# STM32F4_CPU.net
KiCad netlist of a schematic drawn in Altium Designer
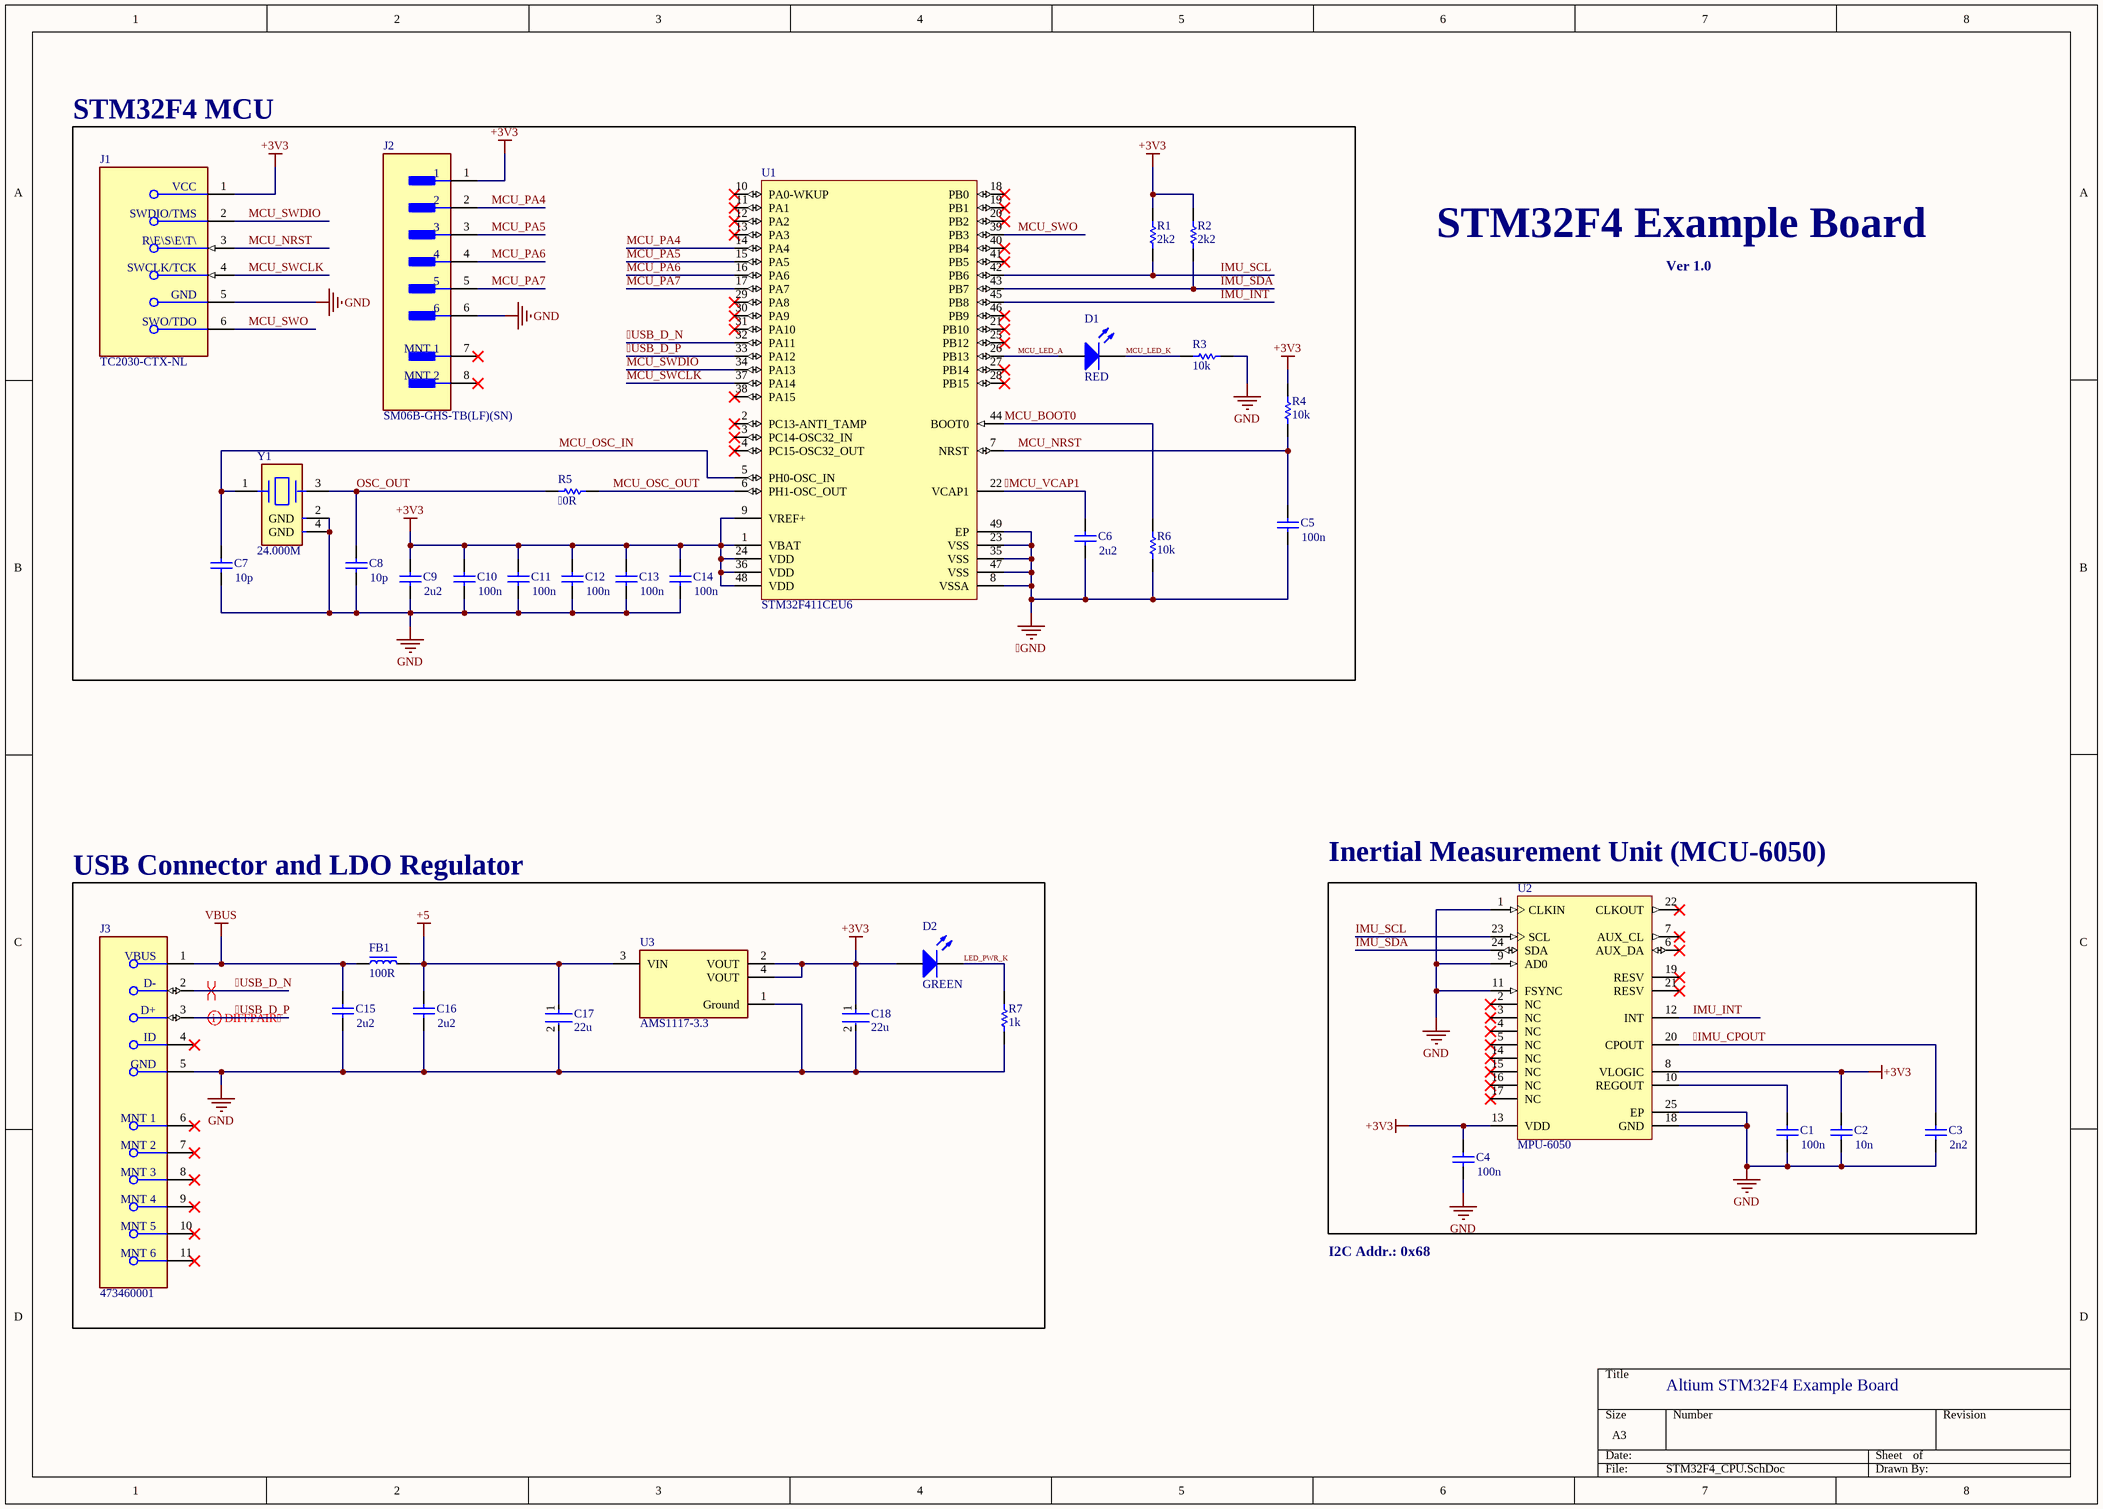
[diagram p0: STM32F4_CPU.SchDoc]

(export (version "E")
  (design (tool "Eeschema 10.0.6"))
  (components
    (comp (ref "C1")
      (value "100n")
      (footprint "0402")
      (description "Capacitor (Semiconductor SIM Model)")
      (fields (field (name "Comment") "Cap Semi") (field (name "PUBLISHER") "Altium Limited"))
      (libsource (lib "Miscellaneous Devices") (part "Cap Semi"))
    )
    (comp (ref "C2")
      (value "10n")
      (footprint "0402")
      (description "Capacitor (Semiconductor SIM Model)")
      (fields (field (name "Comment") "Cap Semi") (field (name "PUBLISHER") "Altium Limited"))
      (libsource (lib "Miscellaneous Devices") (part "Cap Semi"))
    )
    (comp (ref "C3")
      (value "2n2")
      (footprint "0402")
      (description "Capacitor (Semiconductor SIM Model)")
      (fields (field (name "Comment") "Cap Semi") (field (name "PUBLISHER") "Altium Limited"))
      (libsource (lib "Miscellaneous Devices") (part "Cap Semi"))
    )
    (comp (ref "C4")
      (value "100n")
      (footprint "0402")
      (description "Capacitor (Semiconductor SIM Model)")
      (fields (field (name "Comment") "Cap Semi") (field (name "PUBLISHER") "Altium Limited"))
      (libsource (lib "Miscellaneous Devices") (part "Cap Semi"))
    )
    (comp (ref "C5")
      (value "100n")
      (footprint "0402")
      (description "Capacitor (Semiconductor SIM Model)")
      (fields (field (name "Comment") "Cap Semi") (field (name "PUBLISHER") "Altium Limited"))
      (libsource (lib "Miscellaneous Devices") (part "Cap Semi"))
    )
    (comp (ref "C6")
      (value "2u2")
      (footprint "1608[0603]")
      (description "Capacitor (Semiconductor SIM Model)")
      (fields (field (name "Comment") "Cap Semi") (field (name "PUBLISHER") "Altium Limited"))
      (libsource (lib "Miscellaneous Devices") (part "Cap Semi"))
    )
    (comp (ref "C7")
      (value "10p")
      (footprint "0402")
      (description "Capacitor (Semiconductor SIM Model)")
      (fields (field (name "Comment") "Cap Semi") (field (name "PUBLISHER") "Altium Limited"))
      (libsource (lib "Miscellaneous Devices") (part "Cap Semi"))
    )
    (comp (ref "C8")
      (value "10p")
      (footprint "0402")
      (description "Capacitor (Semiconductor SIM Model)")
      (fields (field (name "Comment") "Cap Semi") (field (name "PUBLISHER") "Altium Limited"))
      (libsource (lib "Miscellaneous Devices") (part "Cap Semi"))
    )
    (comp (ref "C9")
      (value "2u2")
      (footprint "1608[0603]")
      (description "Capacitor (Semiconductor SIM Model)")
      (fields (field (name "Comment") "Cap Semi") (field (name "PUBLISHER") "Altium Limited"))
      (libsource (lib "Miscellaneous Devices") (part "Cap Semi"))
    )
    (comp (ref "C10")
      (value "100n")
      (footprint "0402")
      (description "Capacitor (Semiconductor SIM Model)")
      (fields (field (name "Comment") "Cap Semi") (field (name "PUBLISHER") "Altium Limited"))
      (libsource (lib "Miscellaneous Devices") (part "Cap Semi"))
    )
    (comp (ref "C11")
      (value "100n")
      (footprint "0402")
      (description "Capacitor (Semiconductor SIM Model)")
      (fields (field (name "Comment") "Cap Semi") (field (name "PUBLISHER") "Altium Limited"))
      (libsource (lib "Miscellaneous Devices") (part "Cap Semi"))
    )
    (comp (ref "C12")
      (value "100n")
      (footprint "0402")
      (description "Capacitor (Semiconductor SIM Model)")
      (fields (field (name "Comment") "Cap Semi") (field (name "PUBLISHER") "Altium Limited"))
      (libsource (lib "Miscellaneous Devices") (part "Cap Semi"))
    )
    (comp (ref "C13")
      (value "100n")
      (footprint "0402")
      (description "Capacitor (Semiconductor SIM Model)")
      (fields (field (name "Comment") "Cap Semi") (field (name "PUBLISHER") "Altium Limited"))
      (libsource (lib "Miscellaneous Devices") (part "Cap Semi"))
    )
    (comp (ref "C14")
      (value "100n")
      (footprint "0402")
      (description "Capacitor (Semiconductor SIM Model)")
      (fields (field (name "Comment") "Cap Semi") (field (name "PUBLISHER") "Altium Limited"))
      (libsource (lib "Miscellaneous Devices") (part "Cap Semi"))
    )
    (comp (ref "C15")
      (value "2u2")
      (footprint "1608[0603]")
      (description "Capacitor (Semiconductor SIM Model)")
      (fields (field (name "Comment") "Cap Semi") (field (name "PUBLISHER") "Altium Limited"))
      (libsource (lib "Miscellaneous Devices") (part "Cap Semi"))
    )
    (comp (ref "C16")
      (value "2u2")
      (footprint "1608[0603]")
      (description "Capacitor (Semiconductor SIM Model)")
      (fields (field (name "Comment") "Cap Semi") (field (name "PUBLISHER") "Altium Limited"))
      (libsource (lib "Miscellaneous Devices") (part "Cap Semi"))
    )
    (comp (ref "C17")
      (value "22u")
      (footprint "FP-CL21-IPC_A")
      (description "CL21 Series 0805 22uF 16V ±10% Tolerance X5R Multilayer Ceramic Chip Capacitor")
      (fields (field (name "TOLERANCE") "10%"))
      (libsource (lib "Altium Content Vault") (part "b4654b650e69147ec39a6b967a45e02"))
    )
    (comp (ref "C18")
      (value "22u")
      (footprint "FP-CL21-IPC_A")
      (description "CL21 Series 0805 22uF 16V ±10% Tolerance X5R Multilayer Ceramic Chip Capacitor")
      (fields (field (name "TOLERANCE") "10%"))
      (libsource (lib "Altium Content Vault") (part "b4654b650e69147ec39a6b967a45e02"))
    )
    (comp (ref "D1")
      (value "RED")
      (footprint "3.2X1.6X1.1")
      (description "Typical RED, GREEN, YELLOW, AMBER GaAs LED")
      (fields (field (name "PUBLISHER") "Altium Limited"))
      (libsource (lib "Miscellaneous Devices") (part "LED2"))
    )
    (comp (ref "D2")
      (value "GREEN")
      (footprint "3.2X1.6X1.1")
      (description "Typical RED, GREEN, YELLOW, AMBER GaAs LED")
      (fields (field (name "PUBLISHER") "Altium Limited"))
      (libsource (lib "Miscellaneous Devices") (part "LED2"))
    )
    (comp (ref "FB1")
      (value "100R")
      (footprint "FB_0402")
      (description "Ferrite Bead SMD 0402")
      (libsource (lib "Schematic-Lib-PhilsLab") (part "FB_0402"))
    )
    (comp (ref "J1")
      (value "TC2030-CTX-NL")
      (footprint "FP-TC2030-CTX-NL-MFG")
      (description "6-Pin “No legs” TC2030 Plug-of-Nails™ Cable for use with ARM Cortex processors")
      (libsource (lib "Altium Content Vault") (part "e3fe093a55dc37473f431e03719485e"))
    )
    (comp (ref "J2")
      (value "SM06B-GHS-TB(LF)(SN)")
      (footprint "FP-SM06B-GHS-TB_LF_SN-MFG")
      (description "CONN HEADER SMD R/A 6POS 1.25MM")
      (libsource (lib "Altium Content Vault") (part "ed24c53d9ba001d1a2a686240a95171"))
    )
    (comp (ref "J3")
      (value "473460001")
      (footprint "FP-473460001-MFG")
      (description "CONN RCPT USB2.0 MICRO B SMD R/A")
      (fields
        (field (name "OCTOPART") "https://octopart.com/47346-0001-molex-7164928")
        (field (name "MANUFACTURER") "Molex")
      )
      (libsource (lib "Altium Content Vault") (part "53ae1f1d9b557310b43ca686e5bb76a"))
    )
    (comp (ref "R1")
      (value "2k2")
      (footprint "RESC1005X40X25ML05T05")
      (fields (field (name "PART NUMBER") "ERJ-2GEJ103X") (field (name "MANUFACTURER") "Panasonic"))
      (libsource (lib "Altium Content Vault") (part "RES"))
    )
    (comp (ref "R2")
      (value "2k2")
      (footprint "RESC1005X40X25ML05T05")
      (fields (field (name "PART NUMBER") "ERJ-2GEJ103X") (field (name "MANUFACTURER") "Panasonic"))
      (libsource (lib "Altium Content Vault") (part "RES"))
    )
    (comp (ref "R3")
      (value "10k")
      (footprint "RESC1005X40X25ML05T05")
      (fields (field (name "PART NUMBER") "ERJ-2GEJ103X") (field (name "MANUFACTURER") "Panasonic"))
      (libsource (lib "Altium Content Vault") (part "RES"))
    )
    (comp (ref "R4")
      (value "10k")
      (footprint "RESC1005X40X25ML05T05")
      (fields (field (name "PART NUMBER") "ERJ-2GEJ103X") (field (name "MANUFACTURER") "Panasonic"))
      (libsource (lib "Altium Content Vault") (part "RES"))
    )
    (comp (ref "R5")
      (value "0R")
      (footprint "RESC1005X40X25ML05T05")
      (fields (field (name "PART NUMBER") "ERJ-2GEJ103X") (field (name "MANUFACTURER") "Panasonic"))
      (libsource (lib "Altium Content Vault") (part "RES"))
    )
    (comp (ref "R6")
      (value "10k")
      (footprint "RESC1005X40X25ML05T05")
      (fields (field (name "PART NUMBER") "ERJ-2GEJ103X") (field (name "MANUFACTURER") "Panasonic"))
      (libsource (lib "Altium Content Vault") (part "RES"))
    )
    (comp (ref "R7")
      (value "1k")
      (footprint "RESC1005X40X25ML05T05")
      (fields (field (name "PART NUMBER") "ERJ-2GEJ103X") (field (name "MANUFACTURER") "Panasonic"))
      (libsource (lib "Altium Content Vault") (part "RES"))
    )
    (comp (ref "U1")
      (value "STM32F411CEU6")
      (footprint "STM-UFQFPN48_L")
      (libsource (lib "Altium Content Vault") (part "MC-ARM-STM32F411-UFQFPN48"))
    )
    (comp (ref "U2")
      (value "MPU-6050")
      (footprint "IS-QFN-24_V")
      (fields (field (name "MANUFACTURER") "InvenSense"))
      (libsource (lib "Altium Content Vault") (part "IS-MPU-6050-QFN-24"))
    )
    (comp (ref "U3")
      (value "AMS1117-3.3")
      (footprint "FP-AMS1117-IPC_C")
      (description "LDO Voltage Regulators 1A, 3.3V")
      (fields
        (field (name "OCTOPART") "https://octopart.com/ams1117-3.3-advanced+monolithic+systems-25899300")
        (field (name "MANUFACTURER") "Advanced Monolithic Systems")
      )
      (libsource (lib "Altium Content Vault") (part "8bdbb5f8e77002000e30dd2845d0354"))
    )
    (comp (ref "Y1")
      (value "24.000M")
      (footprint "FP-7M-MFG")
      (description "Crystal 24MHz, 10ppm, 10pF, 50Ω")
      (fields (field (name "TOLERANCE") "10ppm"))
      (libsource (lib "Altium Content Vault") (part "41079aabb0e87794b56622915be14ed"))
    )
  )
  (nets
    (net (code "1") (name "GND") (class "Default")
      (node (ref "C5") (pin "1") (pinfunction "1_1") (pintype "passive"))
      (node (ref "C6") (pin "1") (pinfunction "1_1") (pintype "passive"))
      (node (ref "R6") (pin "1") (pinfunction "1_1") (pintype "passive"))
      (node (ref "U1") (pin "23") (pinfunction "VSS_23") (pintype "power_in"))
      (node (ref "U1") (pin "35") (pinfunction "VSS_35") (pintype "power_in"))
      (node (ref "U1") (pin "47") (pinfunction "VSS_47") (pintype "power_in"))
      (node (ref "U1") (pin "49") (pinfunction "EP_49") (pintype "power_in"))
      (node (ref "U1") (pin "8") (pinfunction "VSSA_8") (pintype "power_in"))
    )
    (net (code "2") (name "+3V3") (class "Default")
      (node (ref "C10") (pin "2") (pinfunction "2_2") (pintype "passive"))
      (node (ref "C11") (pin "2") (pinfunction "2_2") (pintype "passive"))
      (node (ref "C12") (pin "2") (pinfunction "2_2") (pintype "passive"))
      (node (ref "C13") (pin "2") (pinfunction "2_2") (pintype "passive"))
      (node (ref "C14") (pin "2") (pinfunction "2_2") (pintype "passive"))
      (node (ref "C18") (pin "1") (pinfunction "1_1") (pintype "passive"))
      (node (ref "C2") (pin "2") (pinfunction "2_2") (pintype "passive"))
      (node (ref "C4") (pin "2") (pinfunction "2_2") (pintype "passive"))
      (node (ref "C9") (pin "2") (pinfunction "2_2") (pintype "passive"))
      (node (ref "D2") (pin "1") (pinfunction "A_1") (pintype "passive"))
      (node (ref "J1") (pin "1") (pinfunction "VCC_1") (pintype "power_in"))
      (node (ref "J2") (pin "1") (pinfunction "1_1") (pintype "passive"))
      (node (ref "R1") (pin "2") (pinfunction "2_2") (pintype "passive"))
      (node (ref "R2") (pin "2") (pinfunction "2_2") (pintype "passive"))
      (node (ref "R4") (pin "2") (pinfunction "2_2") (pintype "passive"))
      (node (ref "U1") (pin "1") (pinfunction "VBAT_1") (pintype "power_in"))
      (node (ref "U1") (pin "24") (pinfunction "VDD_24") (pintype "power_in"))
      (node (ref "U1") (pin "36") (pinfunction "VDD_36") (pintype "power_in"))
      (node (ref "U1") (pin "48") (pinfunction "VDD_48") (pintype "power_in"))
      (node (ref "U1") (pin "9") (pinfunction "VREF+_9") (pintype "power_in"))
      (node (ref "U2") (pin "13") (pinfunction "VDD_13") (pintype "power_in"))
      (node (ref "U2") (pin "8") (pinfunction "VLOGIC_8") (pintype "power_in"))
      (node (ref "U3") (pin "2") (pinfunction "VOUT_2") (pintype "passive"))
      (node (ref "U3") (pin "4") (pinfunction "VOUT_4") (pintype "passive"))
    )
    (net (code "3") (name "+5") (class "Default")
      (node (ref "C16") (pin "2") (pinfunction "2_2") (pintype "passive"))
      (node (ref "C17") (pin "1") (pinfunction "1_1") (pintype "passive"))
      (node (ref "FB1") (pin "2") (pinfunction "2_2") (pintype "passive"))
      (node (ref "U3") (pin "3") (pinfunction "VIN_3") (pintype "power_in"))
    )
    (net (code "4") (name "/IMU_CPOUT") (class "Default")
      (node (ref "C3") (pin "2") (pinfunction "2_2") (pintype "passive"))
      (node (ref "U2") (pin "20") (pinfunction "CPOUT_20") (pintype "passive"))
    )
    (net (code "5") (name "/MCU_VCAP1") (class "Default")
      (node (ref "C6") (pin "2") (pinfunction "2_2") (pintype "passive"))
      (node (ref "U1") (pin "22") (pinfunction "VCAP1_22") (pintype "passive"))
    )
    (net (code "6") (name "/USB_D_N") (class "Default")
      (node (ref "J3") (pin "2") (pinfunction "D-_2") (pintype "bidirectional"))
      (node (ref "U1") (pin "32") (pinfunction "PA11_32") (pintype "bidirectional"))
    )
    (net (code "7") (name "/USB_D_P") (class "Default")
      (node (ref "J3") (pin "3") (pinfunction "D+_3") (pintype "bidirectional"))
      (node (ref "U1") (pin "33") (pinfunction "PA12_33") (pintype "bidirectional"))
    )
    (net (code "8") (name "/IMU_INT") (class "Default")
      (node (ref "U1") (pin "45") (pinfunction "PB8_45") (pintype "bidirectional"))
      (node (ref "U2") (pin "12") (pinfunction "INT_12") (pintype "open_collector"))
    )
    (net (code "9") (name "/IMU_SCL") (class "Default")
      (node (ref "R1") (pin "1") (pinfunction "1_1") (pintype "passive"))
      (node (ref "U1") (pin "42") (pinfunction "PB6_42") (pintype "bidirectional"))
      (node (ref "U2") (pin "23") (pinfunction "SCL_23") (pintype "input"))
    )
    (net (code "10") (name "/IMU_SDA") (class "Default")
      (node (ref "R2") (pin "1") (pinfunction "1_1") (pintype "passive"))
      (node (ref "U1") (pin "43") (pinfunction "PB7_43") (pintype "bidirectional"))
      (node (ref "U2") (pin "24") (pinfunction "SDA_24") (pintype "bidirectional"))
    )
    (net (code "11") (name "/LED_PWR_K") (class "Default")
      (node (ref "D2") (pin "2") (pinfunction "K_2") (pintype "passive"))
      (node (ref "R7") (pin "2") (pinfunction "2_2") (pintype "passive"))
    )
    (net (code "12") (name "/MCU_BOOT0") (class "Default")
      (node (ref "R6") (pin "2") (pinfunction "2_2") (pintype "passive"))
      (node (ref "U1") (pin "44") (pinfunction "BOOT0_44") (pintype "input"))
    )
    (net (code "13") (name "/MCU_LED_A") (class "Default")
      (node (ref "D1") (pin "1") (pinfunction "A_1") (pintype "passive"))
      (node (ref "U1") (pin "26") (pinfunction "PB13_26") (pintype "bidirectional"))
    )
    (net (code "14") (name "/MCU_LED_K") (class "Default")
      (node (ref "D1") (pin "2") (pinfunction "K_2") (pintype "passive"))
      (node (ref "R3") (pin "2") (pinfunction "2_2") (pintype "passive"))
    )
    (net (code "15") (name "/MCU_NRST") (class "Default")
      (node (ref "C5") (pin "2") (pinfunction "2_2") (pintype "passive"))
      (node (ref "J1") (pin "3") (pinfunction "~{RESET}_3") (pintype "input"))
      (node (ref "R4") (pin "1") (pinfunction "1_1") (pintype "passive"))
      (node (ref "U1") (pin "7") (pinfunction "NRST_7") (pintype "bidirectional"))
    )
    (net (code "16") (name "/MCU_OSC_IN") (class "Default")
      (node (ref "C7") (pin "2") (pinfunction "2_2") (pintype "passive"))
      (node (ref "U1") (pin "5") (pinfunction "PH0-OSC_IN_5") (pintype "bidirectional"))
      (node (ref "Y1") (pin "1") (pinfunction "1_1") (pintype "passive"))
    )
    (net (code "17") (name "/MCU_OSC_OUT") (class "Default")
      (node (ref "R5") (pin "1") (pinfunction "1_1") (pintype "passive"))
      (node (ref "U1") (pin "6") (pinfunction "PH1-OSC_OUT_6") (pintype "bidirectional"))
    )
    (net (code "18") (name "/MCU_PA4") (class "Default")
      (node (ref "J2") (pin "2") (pinfunction "2_2") (pintype "passive"))
      (node (ref "U1") (pin "14") (pinfunction "PA4_14") (pintype "bidirectional"))
    )
    (net (code "19") (name "/MCU_PA5") (class "Default")
      (node (ref "J2") (pin "3") (pinfunction "3_3") (pintype "passive"))
      (node (ref "U1") (pin "15") (pinfunction "PA5_15") (pintype "bidirectional"))
    )
    (net (code "20") (name "/MCU_PA6") (class "Default")
      (node (ref "J2") (pin "4") (pinfunction "4_4") (pintype "passive"))
      (node (ref "U1") (pin "16") (pinfunction "PA6_16") (pintype "bidirectional"))
    )
    (net (code "21") (name "/MCU_PA7") (class "Default")
      (node (ref "J2") (pin "5") (pinfunction "5_5") (pintype "passive"))
      (node (ref "U1") (pin "17") (pinfunction "PA7_17") (pintype "bidirectional"))
    )
    (net (code "22") (name "/MCU_SWCLK") (class "Default")
      (node (ref "J1") (pin "4") (pinfunction "SWCLK/TCK_4") (pintype "input"))
      (node (ref "U1") (pin "37") (pinfunction "PA14_37") (pintype "bidirectional"))
    )
    (net (code "23") (name "/MCU_SWDIO") (class "Default")
      (node (ref "J1") (pin "2") (pinfunction "SWDIO/TMS_2") (pintype "passive"))
      (node (ref "U1") (pin "34") (pinfunction "PA13_34") (pintype "bidirectional"))
    )
    (net (code "24") (name "/MCU_SWO") (class "Default")
      (node (ref "J1") (pin "6") (pinfunction "SWO/TDO_6") (pintype "passive"))
      (node (ref "U1") (pin "39") (pinfunction "PB3_39") (pintype "bidirectional"))
    )
    (net (code "25") (name "/OSC_OUT") (class "Default")
      (node (ref "C8") (pin "2") (pinfunction "2_2") (pintype "passive"))
      (node (ref "R5") (pin "2") (pinfunction "2_2") (pintype "passive"))
      (node (ref "Y1") (pin "3") (pinfunction "3_3") (pintype "passive"))
    )
    (net (code "26") (name "GND") (class "Default")
      (node (ref "C1") (pin "1") (pinfunction "1_1") (pintype "passive"))
      (node (ref "C10") (pin "1") (pinfunction "1_1") (pintype "passive"))
      (node (ref "C11") (pin "1") (pinfunction "1_1") (pintype "passive"))
      (node (ref "C12") (pin "1") (pinfunction "1_1") (pintype "passive"))
      (node (ref "C13") (pin "1") (pinfunction "1_1") (pintype "passive"))
      (node (ref "C14") (pin "1") (pinfunction "1_1") (pintype "passive"))
      (node (ref "C15") (pin "1") (pinfunction "1_1") (pintype "passive"))
      (node (ref "C16") (pin "1") (pinfunction "1_1") (pintype "passive"))
      (node (ref "C17") (pin "2") (pinfunction "2_2") (pintype "passive"))
      (node (ref "C18") (pin "2") (pinfunction "2_2") (pintype "passive"))
      (node (ref "C2") (pin "1") (pinfunction "1_1") (pintype "passive"))
      (node (ref "C3") (pin "1") (pinfunction "1_1") (pintype "passive"))
      (node (ref "C4") (pin "1") (pinfunction "1_1") (pintype "passive"))
      (node (ref "C7") (pin "1") (pinfunction "1_1") (pintype "passive"))
      (node (ref "C8") (pin "1") (pinfunction "1_1") (pintype "passive"))
      (node (ref "C9") (pin "1") (pinfunction "1_1") (pintype "passive"))
      (node (ref "J1") (pin "5") (pinfunction "GND_5") (pintype "power_in"))
      (node (ref "J2") (pin "6") (pinfunction "6_6") (pintype "passive"))
      (node (ref "J3") (pin "5") (pinfunction "GND_5") (pintype "power_in"))
      (node (ref "R3") (pin "1") (pinfunction "1_1") (pintype "passive"))
      (node (ref "R7") (pin "1") (pinfunction "1_1") (pintype "passive"))
      (node (ref "U2") (pin "1") (pinfunction "CLKIN_1") (pintype "input"))
      (node (ref "U2") (pin "11") (pinfunction "FSYNC_11") (pintype "input"))
      (node (ref "U2") (pin "18") (pinfunction "GND_18") (pintype "power_in"))
      (node (ref "U2") (pin "25") (pinfunction "EP_25") (pintype "power_in"))
      (node (ref "U2") (pin "9") (pinfunction "AD0_9") (pintype "input"))
      (node (ref "U3") (pin "1") (pinfunction "Ground_1") (pintype "power_in"))
      (node (ref "Y1") (pin "2") (pinfunction "GND_2") (pintype "power_in"))
      (node (ref "Y1") (pin "4") (pinfunction "GND_4") (pintype "power_in"))
    )
    (net (code "27") (name "Net-(U2-REGOUT)") (class "Default")
      (node (ref "C1") (pin "2") (pinfunction "2_2") (pintype "passive"))
      (node (ref "U2") (pin "10") (pinfunction "REGOUT_10") (pintype "passive"))
    )
    (net (code "28") (name "VBUS") (class "Default")
      (node (ref "C15") (pin "2") (pinfunction "2_2") (pintype "passive"))
      (node (ref "FB1") (pin "1") (pinfunction "1_1") (pintype "passive"))
      (node (ref "J3") (pin "1") (pinfunction "VBUS_1") (pintype "power_in"))
    )
    (net (code "29") (name "unconnected-(J2-MNT_1-Pad7)") (class "Default")
      (node (ref "J2") (pin "7") (pinfunction "MNT_1_7") (pintype "passive+no_connect"))
    )
    (net (code "30") (name "unconnected-(J2-MNT_2-Pad8)") (class "Default")
      (node (ref "J2") (pin "8") (pinfunction "MNT_2_8") (pintype "passive+no_connect"))
    )
    (net (code "31") (name "unconnected-(J3-ID-Pad4)") (class "Default")
      (node (ref "J3") (pin "4") (pinfunction "ID_4") (pintype "passive+no_connect"))
    )
    (net (code "32") (name "unconnected-(J3-MNT_1-Pad6)") (class "Default")
      (node (ref "J3") (pin "6") (pinfunction "MNT_1_6") (pintype "passive+no_connect"))
    )
    (net (code "33") (name "unconnected-(J3-MNT_2-Pad7)") (class "Default")
      (node (ref "J3") (pin "7") (pinfunction "MNT_2_7") (pintype "passive+no_connect"))
    )
    (net (code "34") (name "unconnected-(J3-MNT_3-Pad8)") (class "Default")
      (node (ref "J3") (pin "8") (pinfunction "MNT_3_8") (pintype "passive+no_connect"))
    )
    (net (code "35") (name "unconnected-(J3-MNT_4-Pad9)") (class "Default")
      (node (ref "J3") (pin "9") (pinfunction "MNT_4_9") (pintype "passive+no_connect"))
    )
    (net (code "36") (name "unconnected-(J3-MNT_5-Pad10)") (class "Default")
      (node (ref "J3") (pin "10") (pinfunction "MNT_5_10") (pintype "passive+no_connect"))
    )
    (net (code "37") (name "unconnected-(J3-MNT_6-Pad11)") (class "Default")
      (node (ref "J3") (pin "11") (pinfunction "MNT_6_11") (pintype "passive+no_connect"))
    )
    (net (code "38") (name "unconnected-(U1-PA0-WKUP-Pad10)") (class "Default")
      (node (ref "U1") (pin "10") (pinfunction "PA0-WKUP_10") (pintype "bidirectional+no_connect"))
    )
    (net (code "39") (name "unconnected-(U1-PA1-Pad11)") (class "Default")
      (node (ref "U1") (pin "11") (pinfunction "PA1_11") (pintype "bidirectional+no_connect"))
    )
    (net (code "40") (name "unconnected-(U1-PA2-Pad12)") (class "Default")
      (node (ref "U1") (pin "12") (pinfunction "PA2_12") (pintype "bidirectional+no_connect"))
    )
    (net (code "41") (name "unconnected-(U1-PA3-Pad13)") (class "Default")
      (node (ref "U1") (pin "13") (pinfunction "PA3_13") (pintype "bidirectional+no_connect"))
    )
    (net (code "42") (name "unconnected-(U1-PA8-Pad29)") (class "Default")
      (node (ref "U1") (pin "29") (pinfunction "PA8_29") (pintype "bidirectional+no_connect"))
    )
    (net (code "43") (name "unconnected-(U1-PA9-Pad30)") (class "Default")
      (node (ref "U1") (pin "30") (pinfunction "PA9_30") (pintype "bidirectional+no_connect"))
    )
    (net (code "44") (name "unconnected-(U1-PA10-Pad31)") (class "Default")
      (node (ref "U1") (pin "31") (pinfunction "PA10_31") (pintype "bidirectional+no_connect"))
    )
    (net (code "45") (name "unconnected-(U1-PA15-Pad38)") (class "Default")
      (node (ref "U1") (pin "38") (pinfunction "PA15_38") (pintype "bidirectional+no_connect"))
    )
    (net (code "46") (name "unconnected-(U1-PB0-Pad18)") (class "Default")
      (node (ref "U1") (pin "18") (pinfunction "PB0_18") (pintype "bidirectional+no_connect"))
    )
    (net (code "47") (name "unconnected-(U1-PB1-Pad19)") (class "Default")
      (node (ref "U1") (pin "19") (pinfunction "PB1_19") (pintype "bidirectional+no_connect"))
    )
    (net (code "48") (name "unconnected-(U1-PB2-Pad20)") (class "Default")
      (node (ref "U1") (pin "20") (pinfunction "PB2_20") (pintype "bidirectional+no_connect"))
    )
    (net (code "49") (name "unconnected-(U1-PB4-Pad40)") (class "Default")
      (node (ref "U1") (pin "40") (pinfunction "PB4_40") (pintype "bidirectional+no_connect"))
    )
    (net (code "50") (name "unconnected-(U1-PB5-Pad41)") (class "Default")
      (node (ref "U1") (pin "41") (pinfunction "PB5_41") (pintype "bidirectional+no_connect"))
    )
    (net (code "51") (name "unconnected-(U1-PB9-Pad46)") (class "Default")
      (node (ref "U1") (pin "46") (pinfunction "PB9_46") (pintype "bidirectional+no_connect"))
    )
    (net (code "52") (name "unconnected-(U1-PB10-Pad21)") (class "Default")
      (node (ref "U1") (pin "21") (pinfunction "PB10_21") (pintype "bidirectional+no_connect"))
    )
    (net (code "53") (name "unconnected-(U1-PB12-Pad25)") (class "Default")
      (node (ref "U1") (pin "25") (pinfunction "PB12_25") (pintype "bidirectional+no_connect"))
    )
    (net (code "54") (name "unconnected-(U1-PB14-Pad27)") (class "Default")
      (node (ref "U1") (pin "27") (pinfunction "PB14_27") (pintype "bidirectional+no_connect"))
    )
    (net (code "55") (name "unconnected-(U1-PB15-Pad28)") (class "Default")
      (node (ref "U1") (pin "28") (pinfunction "PB15_28") (pintype "bidirectional+no_connect"))
    )
    (net (code "56") (name "unconnected-(U1-PC13-ANTI_TAMP-Pad2)") (class "Default")
      (node (ref "U1") (pin "2") (pinfunction "PC13-ANTI_TAMP_2") (pintype "bidirectional+no_connect"))
    )
    (net (code "57") (name "unconnected-(U1-PC14-OSC32_IN-Pad3)") (class "Default")
      (node (ref "U1") (pin "3") (pinfunction "PC14-OSC32_IN_3") (pintype "bidirectional+no_connect"))
    )
    (net (code "58") (name "unconnected-(U1-PC15-OSC32_OUT-Pad4)") (class "Default")
      (node (ref "U1") (pin "4") (pinfunction "PC15-OSC32_OUT_4") (pintype "bidirectional+no_connect"))
    )
    (net (code "59") (name "unconnected-(U2-AUX_CL-Pad7)") (class "Default")
      (node (ref "U2") (pin "7") (pinfunction "AUX_CL_7") (pintype "output+no_connect"))
    )
    (net (code "60") (name "unconnected-(U2-AUX_DA-Pad6)") (class "Default")
      (node (ref "U2") (pin "6") (pinfunction "AUX_DA_6") (pintype "bidirectional+no_connect"))
    )
    (net (code "61") (name "unconnected-(U2-CLKOUT-Pad22)") (class "Default")
      (node (ref "U2") (pin "22") (pinfunction "CLKOUT_22") (pintype "output+no_connect"))
    )
    (net (code "62") (name "unconnected-(U2-NC-Pad2)") (class "Default")
      (node (ref "U2") (pin "2") (pinfunction "NC_2") (pintype "passive+no_connect"))
    )
    (net (code "63") (name "unconnected-(U2-NC-Pad3)") (class "Default")
      (node (ref "U2") (pin "3") (pinfunction "NC_3") (pintype "passive+no_connect"))
    )
    (net (code "64") (name "unconnected-(U2-NC-Pad4)") (class "Default")
      (node (ref "U2") (pin "4") (pinfunction "NC_4") (pintype "passive+no_connect"))
    )
    (net (code "65") (name "unconnected-(U2-NC-Pad5)") (class "Default")
      (node (ref "U2") (pin "5") (pinfunction "NC_5") (pintype "passive+no_connect"))
    )
    (net (code "66") (name "unconnected-(U2-NC-Pad14)") (class "Default")
      (node (ref "U2") (pin "14") (pinfunction "NC_14") (pintype "passive+no_connect"))
    )
    (net (code "67") (name "unconnected-(U2-NC-Pad15)") (class "Default")
      (node (ref "U2") (pin "15") (pinfunction "NC_15") (pintype "passive+no_connect"))
    )
    (net (code "68") (name "unconnected-(U2-NC-Pad16)") (class "Default")
      (node (ref "U2") (pin "16") (pinfunction "NC_16") (pintype "passive+no_connect"))
    )
    (net (code "69") (name "unconnected-(U2-NC-Pad17)") (class "Default")
      (node (ref "U2") (pin "17") (pinfunction "NC_17") (pintype "passive+no_connect"))
    )
    (net (code "70") (name "unconnected-(U2-RESV-Pad19)") (class "Default")
      (node (ref "U2") (pin "19") (pinfunction "RESV_19") (pintype "passive+no_connect"))
    )
    (net (code "71") (name "unconnected-(U2-RESV-Pad21)") (class "Default")
      (node (ref "U2") (pin "21") (pinfunction "RESV_21") (pintype "passive+no_connect"))
    )
  )
)
